# Joe_final_hack3.net
KiCad netlist of a schematic drawn in EAGLE
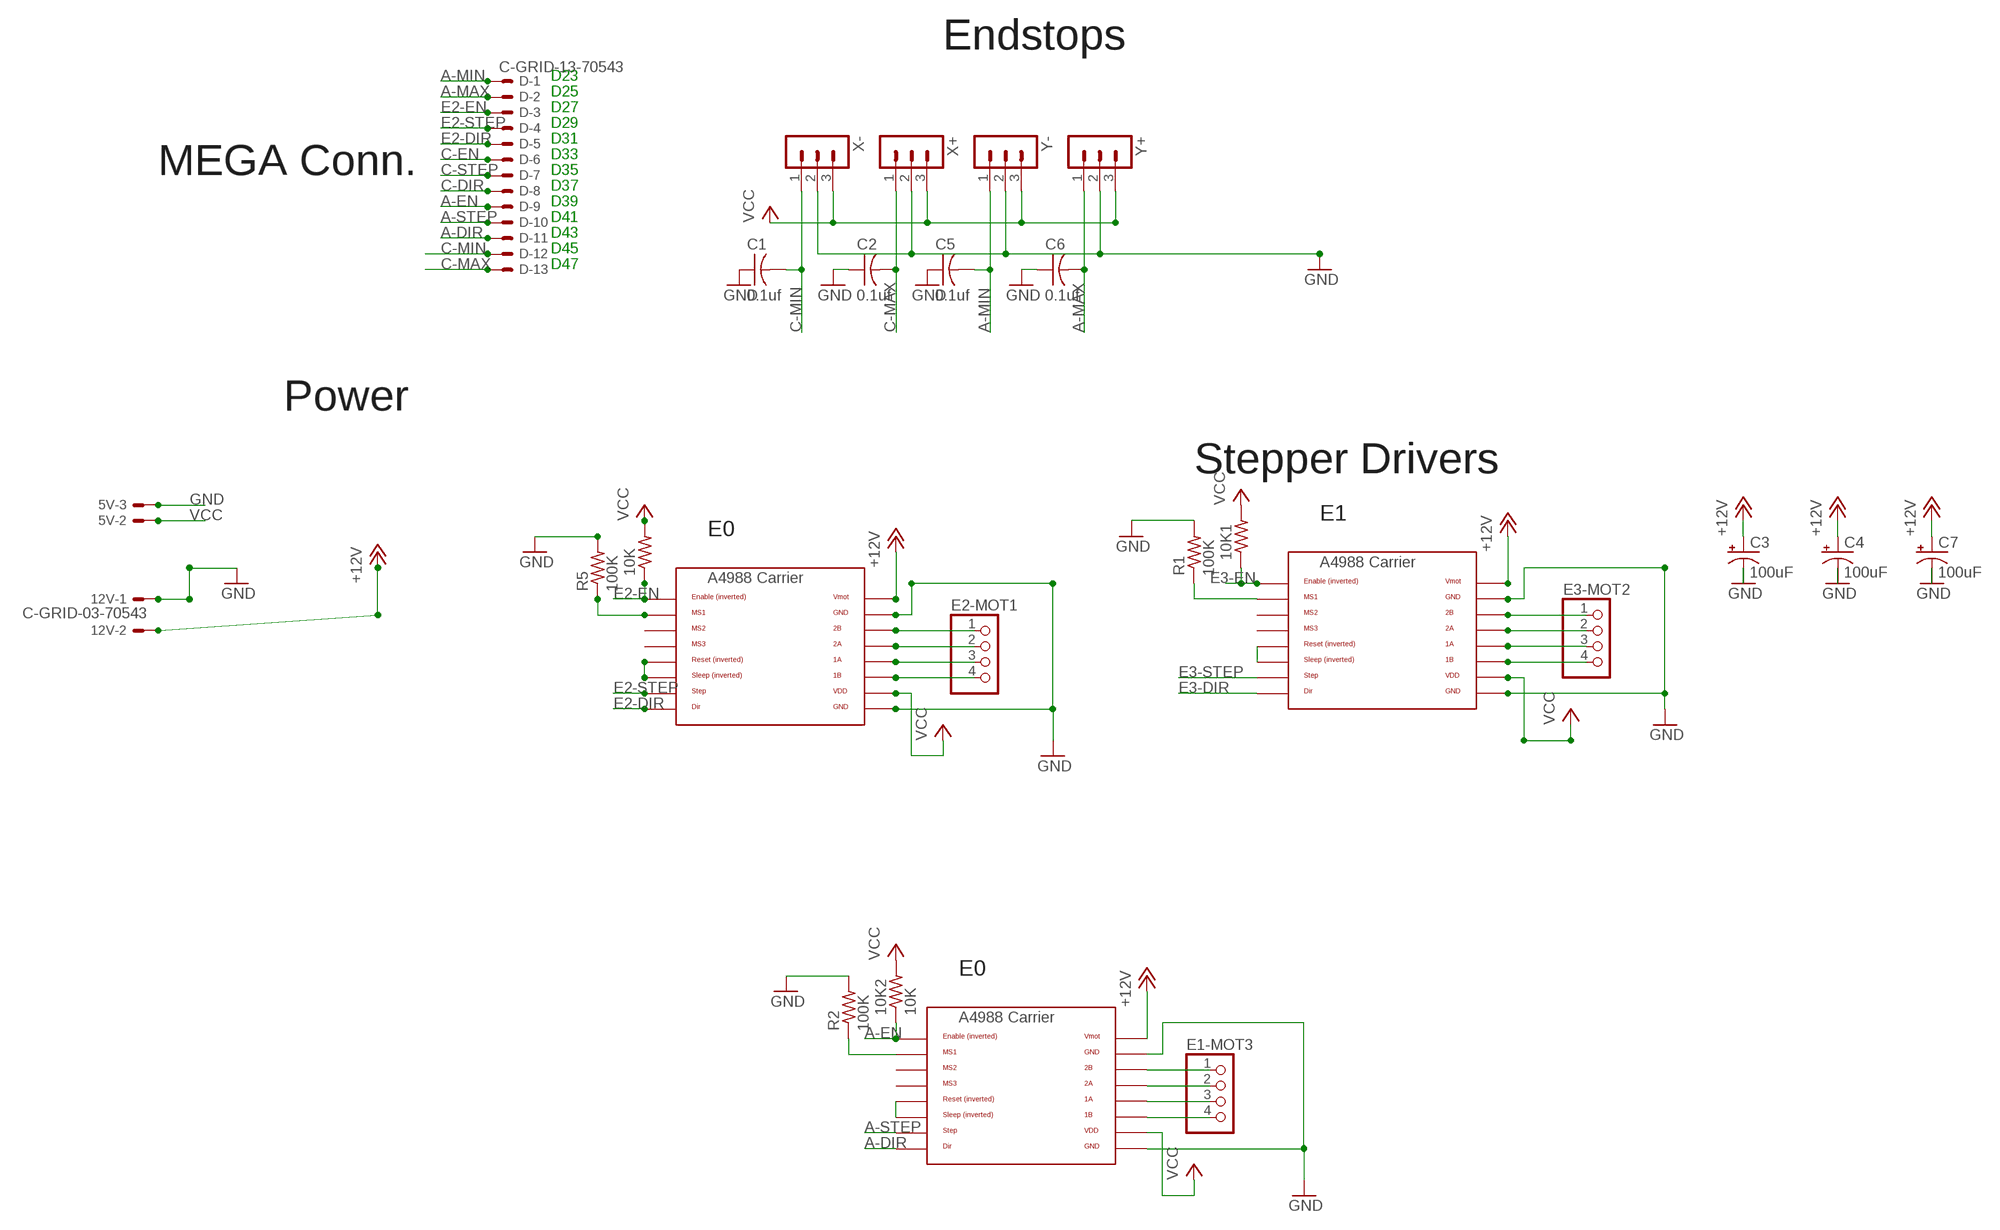
[diagram p0: schematic, sheet 1]

(export (version "E")
  (design (tool "Eeschema 10.0.6"))
  (components
    (comp (ref "5V")
      (value "C-GRID-03-70543")
      (footprint "eagle-import:70543-03")
      (libsource (lib "eagle-import") (part "C-GRID-03-70543"))
    )
    (comp (ref "10K")
      (value "RES-US1206FAB")
      (footprint "eagle-import:R1206FAB")
      (libsource (lib "eagle-import") (part "RES-US1206FAB"))
    )
    (comp (ref "10K1")
      (value "RES-US1206FAB")
      (footprint "eagle-import:R1206FAB")
      (libsource (lib "eagle-import") (part "RES-US1206FAB"))
    )
    (comp (ref "10K2")
      (value "10K")
      (footprint "eagle-import:R1206FAB")
      (libsource (lib "eagle-import") (part "RES-US1206FAB"))
    )
    (comp (ref "12V")
      (value "C-GRID-03-70543")
      (footprint "eagle-import:70543-03")
      (libsource (lib "eagle-import") (part "C-GRID-03-70543"))
    )
    (comp (ref "C1")
      (value "0.1uf")
      (footprint "eagle-import:C1206FAB")
      (libsource (lib "eagle-import") (part "CAP-US1206FAB"))
    )
    (comp (ref "C2")
      (value "0.1uf")
      (footprint "eagle-import:C1206FAB")
      (libsource (lib "eagle-import") (part "CAP-US1206FAB"))
    )
    (comp (ref "C3")
      (value "100uF")
      (footprint "eagle-import:153CLV-0605")
      (libsource (lib "eagle-import") (part "CPOL-US153CLV-0605"))
    )
    (comp (ref "C4")
      (value "100uF")
      (footprint "eagle-import:153CLV-0605")
      (libsource (lib "eagle-import") (part "CPOL-US153CLV-0605"))
    )
    (comp (ref "C5")
      (value "0.1uf")
      (footprint "eagle-import:C1206FAB")
      (libsource (lib "eagle-import") (part "CAP-US1206FAB"))
    )
    (comp (ref "C6")
      (value "0.1uf")
      (footprint "eagle-import:C1206FAB")
      (libsource (lib "eagle-import") (part "CAP-US1206FAB"))
    )
    (comp (ref "C7")
      (value "100uF")
      (footprint "eagle-import:153CLV-0605")
      (libsource (lib "eagle-import") (part "CPOL-US153CLV-0605"))
    )
    (comp (ref "D")
      (value "C-GRID-13-70543")
      (footprint "eagle-import:70543-13")
      (libsource (lib "eagle-import") (part "C-GRID-13-70543"))
    )
    (comp (ref "E1-MOT3")
      (value "PINHD-1X4")
      (footprint "eagle-import:1X04")
      (libsource (lib "eagle-import") (part "PINHD-1X4"))
    )
    (comp (ref "E2-MOT1")
      (value "PINHD-1X4")
      (footprint "eagle-import:1X04")
      (libsource (lib "eagle-import") (part "PINHD-1X4"))
    )
    (comp (ref "E3-MOT2")
      (value "PINHD-1X4")
      (footprint "eagle-import:1X04")
      (libsource (lib "eagle-import") (part "PINHD-1X4"))
    )
    (comp (ref "R1")
      (value "100K")
      (footprint "eagle-import:R1206FAB")
      (libsource (lib "eagle-import") (part "RES-US1206FAB"))
    )
    (comp (ref "R2")
      (value "100K")
      (footprint "eagle-import:R1206FAB")
      (libsource (lib "eagle-import") (part "RES-US1206FAB"))
    )
    (comp (ref "R5")
      (value "100K")
      (footprint "eagle-import:R1206FAB")
      (libsource (lib "eagle-import") (part "RES-US1206FAB"))
    )
    (comp (ref "U$1")
      (value "A4988BREAKOUT")
      (footprint "eagle-import:A4988BREAKOUT")
      (libsource (lib "eagle-import") (part "A4988BREAKOUT"))
    )
    (comp (ref "U$4")
      (value "A4988BREAKOUT")
      (footprint "eagle-import:A4988BREAKOUT")
      (libsource (lib "eagle-import") (part "A4988BREAKOUT"))
    )
    (comp (ref "U$5")
      (value "A4988BREAKOUT")
      (footprint "eagle-import:A4988BREAKOUT")
      (libsource (lib "eagle-import") (part "A4988BREAKOUT"))
    )
    (comp (ref "X+")
      (value "3PIN-HEADER")
      (footprint "eagle-import:3PIN-HEADER")
      (libsource (lib "eagle-import") (part "3PIN-HEADER"))
    )
    (comp (ref "X-")
      (value "3PIN-HEADER")
      (footprint "eagle-import:3PIN-HEADER")
      (libsource (lib "eagle-import") (part "3PIN-HEADER"))
    )
    (comp (ref "Y+")
      (value "3PIN-HEADER")
      (footprint "eagle-import:3PIN-HEADER")
      (libsource (lib "eagle-import") (part "3PIN-HEADER"))
    )
    (comp (ref "Y-")
      (value "3PIN-HEADER")
      (footprint "eagle-import:3PIN-HEADER")
      (libsource (lib "eagle-import") (part "3PIN-HEADER"))
    )
  )
  (nets
    (net (code "1") (name "+12V") (class "Default")
      (node (ref "12V") (pin "2") (pinfunction "S_2") (pintype "passive"))
      (node (ref "C3") (pin "+") (pinfunction "+_+") (pintype "passive"))
      (node (ref "C4") (pin "+") (pinfunction "+_+") (pintype "passive"))
      (node (ref "C7") (pin "+") (pinfunction "+_+") (pintype "passive"))
      (node (ref "U$1") (pin "VMOT") (pinfunction "VMOT_VMOT") (pintype "power_in"))
      (node (ref "U$4") (pin "VMOT") (pinfunction "VMOT_VMOT") (pintype "power_in"))
      (node (ref "U$5") (pin "VMOT") (pinfunction "VMOT_VMOT") (pintype "power_in"))
    )
    (net (code "2") (name "/A-DIR") (class "Default")
      (node (ref "D") (pin "11") (pinfunction "S_11") (pintype "passive"))
      (node (ref "U$1") (pin "DIR") (pinfunction "DIR_DIR") (pintype "input"))
    )
    (net (code "3") (name "/A-EN") (class "Default")
      (node (ref "10K2") (pin "1") (pinfunction "1_1") (pintype "passive"))
      (node (ref "D") (pin "9") (pinfunction "S_9") (pintype "passive"))
      (node (ref "U$1") (pin "EN") (pinfunction "EN_EN") (pintype "input"))
    )
    (net (code "4") (name "/A-MAX") (class "Default")
      (node (ref "C6") (pin "2") (pinfunction "2_2") (pintype "passive"))
      (node (ref "D") (pin "2") (pinfunction "S_2") (pintype "passive"))
      (node (ref "Y+") (pin "1") (pinfunction "1_1") (pintype "passive"))
    )
    (net (code "5") (name "/A-MIN") (class "Default")
      (node (ref "C5") (pin "2") (pinfunction "2_2") (pintype "passive"))
      (node (ref "D") (pin "1") (pinfunction "S_1") (pintype "passive"))
      (node (ref "Y-") (pin "1") (pinfunction "1_1") (pintype "passive"))
    )
    (net (code "6") (name "/A-STEP") (class "Default")
      (node (ref "D") (pin "10") (pinfunction "S_10") (pintype "passive"))
      (node (ref "U$1") (pin "STEP") (pinfunction "STEP_STEP") (pintype "input"))
    )
    (net (code "7") (name "/C-DIR") (class "Default")
      (node (ref "D") (pin "8") (pinfunction "S_8") (pintype "passive"))
    )
    (net (code "8") (name "/C-EN") (class "Default")
      (node (ref "D") (pin "6") (pinfunction "S_6") (pintype "passive"))
    )
    (net (code "9") (name "/C-MAX") (class "Default")
      (node (ref "C2") (pin "2") (pinfunction "2_2") (pintype "passive"))
      (node (ref "D") (pin "13") (pinfunction "S_13") (pintype "passive"))
      (node (ref "X+") (pin "1") (pinfunction "1_1") (pintype "passive"))
    )
    (net (code "10") (name "/C-MIN") (class "Default")
      (node (ref "C1") (pin "2") (pinfunction "2_2") (pintype "passive"))
      (node (ref "D") (pin "12") (pinfunction "S_12") (pintype "passive"))
      (node (ref "X-") (pin "1") (pinfunction "1_1") (pintype "passive"))
    )
    (net (code "11") (name "/C-STEP") (class "Default")
      (node (ref "D") (pin "7") (pinfunction "S_7") (pintype "passive"))
    )
    (net (code "12") (name "/E2-DIR") (class "Default")
      (node (ref "D") (pin "5") (pinfunction "S_5") (pintype "passive"))
      (node (ref "U$4") (pin "DIR") (pinfunction "DIR_DIR") (pintype "input"))
    )
    (net (code "13") (name "/E2-EN") (class "Default")
      (node (ref "10K") (pin "1") (pinfunction "1_1") (pintype "passive"))
      (node (ref "D") (pin "3") (pinfunction "S_3") (pintype "passive"))
      (node (ref "U$4") (pin "EN") (pinfunction "EN_EN") (pintype "input"))
    )
    (net (code "14") (name "/E2-STEP") (class "Default")
      (node (ref "D") (pin "4") (pinfunction "S_4") (pintype "passive"))
      (node (ref "U$4") (pin "STEP") (pinfunction "STEP_STEP") (pintype "input"))
    )
    (net (code "15") (name "/E3-DIR") (class "Default")
      (node (ref "U$5") (pin "DIR") (pinfunction "DIR_DIR") (pintype "input"))
    )
    (net (code "16") (name "/E3-EN") (class "Default")
      (node (ref "10K1") (pin "1") (pinfunction "1_1") (pintype "passive"))
      (node (ref "U$5") (pin "EN") (pinfunction "EN_EN") (pintype "input"))
    )
    (net (code "17") (name "/E3-STEP") (class "Default")
      (node (ref "U$5") (pin "STEP") (pinfunction "STEP_STEP") (pintype "input"))
    )
    (net (code "18") (name "GND") (class "Default")
      (node (ref "12V") (pin "1") (pinfunction "S_1") (pintype "passive"))
      (node (ref "5V") (pin "3") (pinfunction "S_3") (pintype "passive"))
      (node (ref "C1") (pin "1") (pinfunction "1_1") (pintype "passive"))
      (node (ref "C2") (pin "1") (pinfunction "1_1") (pintype "passive"))
      (node (ref "C3") (pin "-") (pinfunction "-_-") (pintype "passive"))
      (node (ref "C4") (pin "-") (pinfunction "-_-") (pintype "passive"))
      (node (ref "C5") (pin "1") (pinfunction "1_1") (pintype "passive"))
      (node (ref "C6") (pin "1") (pinfunction "1_1") (pintype "passive"))
      (node (ref "C7") (pin "-") (pinfunction "-_-") (pintype "passive"))
      (node (ref "R1") (pin "2") (pinfunction "2_2") (pintype "passive"))
      (node (ref "R2") (pin "2") (pinfunction "2_2") (pintype "passive"))
      (node (ref "R5") (pin "2") (pinfunction "2_2") (pintype "passive"))
      (node (ref "U$1") (pin "GND") (pinfunction "GND_GND") (pintype "power_in"))
      (node (ref "U$1") (pin "GND@0") (pinfunction "GND_GND@0") (pintype "power_in"))
      (node (ref "U$4") (pin "GND") (pinfunction "GND_GND") (pintype "power_in"))
      (node (ref "U$4") (pin "GND@0") (pinfunction "GND_GND@0") (pintype "power_in"))
      (node (ref "U$5") (pin "GND") (pinfunction "GND_GND") (pintype "power_in"))
      (node (ref "U$5") (pin "GND@0") (pinfunction "GND_GND@0") (pintype "power_in"))
      (node (ref "X+") (pin "2") (pinfunction "2_2") (pintype "passive"))
      (node (ref "X-") (pin "2") (pinfunction "2_2") (pintype "passive"))
      (node (ref "Y+") (pin "2") (pinfunction "2_2") (pintype "passive"))
      (node (ref "Y-") (pin "2") (pinfunction "2_2") (pintype "passive"))
    )
    (net (code "19") (name "Net-(E1-MOT3-Pad1)") (class "Default")
      (node (ref "E1-MOT3") (pin "1") (pinfunction "1_1") (pintype "passive"))
      (node (ref "U$1") (pin "2B") (pinfunction "2B_2B") (pintype "output"))
    )
    (net (code "20") (name "Net-(E1-MOT3-Pad2)") (class "Default")
      (node (ref "E1-MOT3") (pin "2") (pinfunction "2_2") (pintype "passive"))
      (node (ref "U$1") (pin "2A") (pinfunction "2A_2A") (pintype "output"))
    )
    (net (code "21") (name "Net-(E1-MOT3-Pad3)") (class "Default")
      (node (ref "E1-MOT3") (pin "3") (pinfunction "3_3") (pintype "passive"))
      (node (ref "U$1") (pin "1A") (pinfunction "1A_1A") (pintype "output"))
    )
    (net (code "22") (name "Net-(E1-MOT3-Pad4)") (class "Default")
      (node (ref "E1-MOT3") (pin "4") (pinfunction "4_4") (pintype "passive"))
      (node (ref "U$1") (pin "1B") (pinfunction "1B_1B") (pintype "output"))
    )
    (net (code "23") (name "Net-(E2-MOT1-Pad1)") (class "Default")
      (node (ref "E2-MOT1") (pin "1") (pinfunction "1_1") (pintype "passive"))
      (node (ref "U$4") (pin "2B") (pinfunction "2B_2B") (pintype "output"))
    )
    (net (code "24") (name "Net-(E2-MOT1-Pad2)") (class "Default")
      (node (ref "E2-MOT1") (pin "2") (pinfunction "2_2") (pintype "passive"))
      (node (ref "U$4") (pin "2A") (pinfunction "2A_2A") (pintype "output"))
    )
    (net (code "25") (name "Net-(E2-MOT1-Pad3)") (class "Default")
      (node (ref "E2-MOT1") (pin "3") (pinfunction "3_3") (pintype "passive"))
      (node (ref "U$4") (pin "1A") (pinfunction "1A_1A") (pintype "output"))
    )
    (net (code "26") (name "Net-(E2-MOT1-Pad4)") (class "Default")
      (node (ref "E2-MOT1") (pin "4") (pinfunction "4_4") (pintype "passive"))
      (node (ref "U$4") (pin "1B") (pinfunction "1B_1B") (pintype "output"))
    )
    (net (code "27") (name "Net-(E3-MOT2-Pad1)") (class "Default")
      (node (ref "E3-MOT2") (pin "1") (pinfunction "1_1") (pintype "passive"))
      (node (ref "U$5") (pin "2B") (pinfunction "2B_2B") (pintype "output"))
    )
    (net (code "28") (name "Net-(E3-MOT2-Pad2)") (class "Default")
      (node (ref "E3-MOT2") (pin "2") (pinfunction "2_2") (pintype "passive"))
      (node (ref "U$5") (pin "2A") (pinfunction "2A_2A") (pintype "output"))
    )
    (net (code "29") (name "Net-(E3-MOT2-Pad3)") (class "Default")
      (node (ref "E3-MOT2") (pin "3") (pinfunction "3_3") (pintype "passive"))
      (node (ref "U$5") (pin "1A") (pinfunction "1A_1A") (pintype "output"))
    )
    (net (code "30") (name "Net-(E3-MOT2-Pad4)") (class "Default")
      (node (ref "E3-MOT2") (pin "4") (pinfunction "4_4") (pintype "passive"))
      (node (ref "U$5") (pin "1B") (pinfunction "1B_1B") (pintype "output"))
    )
    (net (code "31") (name "Net-(R1-Pad1)") (class "Default")
      (node (ref "R1") (pin "1") (pinfunction "1_1") (pintype "passive"))
      (node (ref "U$5") (pin "MS1") (pinfunction "MS1_MS1") (pintype "input"))
    )
    (net (code "32") (name "Net-(R2-Pad1)") (class "Default")
      (node (ref "R2") (pin "1") (pinfunction "1_1") (pintype "passive"))
      (node (ref "U$1") (pin "MS1") (pinfunction "MS1_MS1") (pintype "input"))
    )
    (net (code "33") (name "Net-(R5-Pad1)") (class "Default")
      (node (ref "R5") (pin "1") (pinfunction "1_1") (pintype "passive"))
      (node (ref "U$4") (pin "MS1") (pinfunction "MS1_MS1") (pintype "input"))
    )
    (net (code "34") (name "Net-(U$1-SLEEP)") (class "Default")
      (node (ref "U$1") (pin "RST") (pinfunction "RST_RST") (pintype "input"))
      (node (ref "U$1") (pin "SLP") (pinfunction "SLEEP_SLP") (pintype "input"))
    )
    (net (code "35") (name "Net-(U$4-SLEEP)") (class "Default")
      (node (ref "U$4") (pin "RST") (pinfunction "RST_RST") (pintype "input"))
      (node (ref "U$4") (pin "SLP") (pinfunction "SLEEP_SLP") (pintype "input"))
    )
    (net (code "36") (name "Net-(U$5-SLEEP)") (class "Default")
      (node (ref "U$5") (pin "RST") (pinfunction "RST_RST") (pintype "input"))
      (node (ref "U$5") (pin "SLP") (pinfunction "SLEEP_SLP") (pintype "input"))
    )
    (net (code "37") (name "VCC") (class "Default")
      (node (ref "10K") (pin "2") (pinfunction "2_2") (pintype "passive"))
      (node (ref "10K1") (pin "2") (pinfunction "2_2") (pintype "passive"))
      (node (ref "10K2") (pin "2") (pinfunction "2_2") (pintype "passive"))
      (node (ref "5V") (pin "2") (pinfunction "S_2") (pintype "passive"))
      (node (ref "U$1") (pin "VDD") (pinfunction "VDD_VDD") (pintype "power_in"))
      (node (ref "U$4") (pin "VDD") (pinfunction "VDD_VDD") (pintype "power_in"))
      (node (ref "U$5") (pin "VDD") (pinfunction "VDD_VDD") (pintype "power_in"))
      (node (ref "X+") (pin "3") (pinfunction "3_3") (pintype "passive"))
      (node (ref "X-") (pin "3") (pinfunction "3_3") (pintype "passive"))
      (node (ref "Y+") (pin "3") (pinfunction "3_3") (pintype "passive"))
      (node (ref "Y-") (pin "3") (pinfunction "3_3") (pintype "passive"))
    )
    (net (code "38") (name "unconnected-(U$1-PadMS2)") (class "Default")
      (node (ref "U$1") (pin "MS2") (pinfunction "MS2_MS2") (pintype "input"))
    )
    (net (code "39") (name "unconnected-(U$1-PadMS3)") (class "Default")
      (node (ref "U$1") (pin "MS3") (pinfunction "MS3_MS3") (pintype "input"))
    )
    (net (code "40") (name "unconnected-(U$4-PadMS2)") (class "Default")
      (node (ref "U$4") (pin "MS2") (pinfunction "MS2_MS2") (pintype "input"))
    )
    (net (code "41") (name "unconnected-(U$4-PadMS3)") (class "Default")
      (node (ref "U$4") (pin "MS3") (pinfunction "MS3_MS3") (pintype "input"))
    )
    (net (code "42") (name "unconnected-(U$5-PadMS2)") (class "Default")
      (node (ref "U$5") (pin "MS2") (pinfunction "MS2_MS2") (pintype "input"))
    )
    (net (code "43") (name "unconnected-(U$5-PadMS3)") (class "Default")
      (node (ref "U$5") (pin "MS3") (pinfunction "MS3_MS3") (pintype "input"))
    )
  )
)
